# INA.net
KiCad netlist of a schematic drawn in Altium Designer
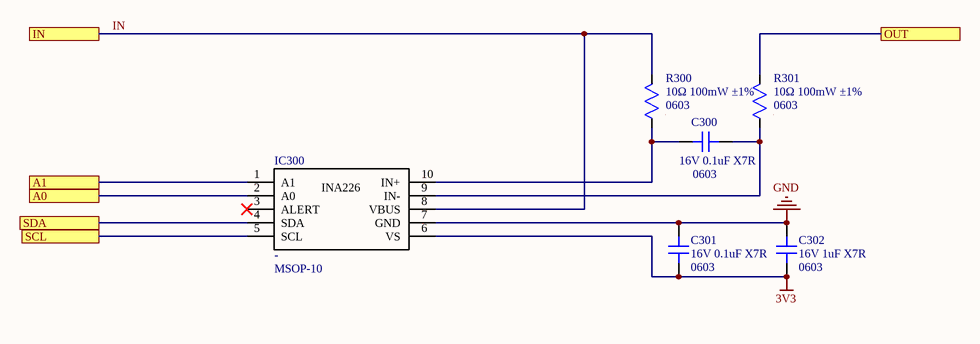
[diagram p0: INA.SchDoc]

(export (version "E")
  (design (tool "Eeschema 10.0.6"))
  (components
    (comp (ref "C300")
      (value "16V 0.1uF X7R")
      (footprint "CAP SMD 0603")
      (description "Condensadores de cerámica multicapa (MLCC- SMD/SMT) WCAP-CSGP 0.1uF 0603 10% 16V MLCC")
      (fields
        (field (name "PACKAGE") "0603")
        (field (name "MPN") "885012206046")
        (field (name "MANUFACTURER") "Wurth Elektronik")
      )
      (libsource (lib "eUSR_Database") (part "CAP non polarized"))
    )
    (comp (ref "C301")
      (value "16V 0.1uF X7R")
      (footprint "CAP SMD 0603")
      (description "Condensadores de cerámica multicapa (MLCC- SMD/SMT) WCAP-CSGP 0.1uF 0603 10% 16V MLCC")
      (fields
        (field (name "PACKAGE") "0603")
        (field (name "MPN") "885012206046")
        (field (name "MANUFACTURER") "Wurth Elektronik")
      )
      (libsource (lib "eUSR_Database") (part "CAP non polarized"))
    )
    (comp (ref "C302")
      (value "16V 1uF X7R")
      (footprint "CAP SMD 0603")
      (description "Condensadores de cerámica multicapa (MLCC- SMD/SMT) WCAP-CSGP 1uF 0603 10% 16V MLCC")
      (fields
        (field (name "PACKAGE") "0603")
        (field (name "MPN") "885012206052")
        (field (name "MANUFACTURER") "Wurth Elektronik")
      )
      (libsource (lib "eUSR_Database") (part "CAP non polarized"))
    )
    (comp (ref "IC300")
      (value "-")
      (footprint "VSOP-10")
      (fields
        (field (name "PACKAGE") "MSOP-10")
        (field (name "MPN") "INA226AIDGSR")
        (field (name "MANUFACTURER") "595-INA226AIDGSR")
        (field (name "Comment") "INA226")
      )
      (libsource (lib "eUSR_Database") (part "INA226"))
    )
    (comp (ref "R300")
      (value "10Ω 100mW ±1%")
      (footprint "RES SMD 0603")
      (description "Resistores de película gruesa - SMD WRIS-RSKS 10 Ohms 1 % 0.1 W 0603 AEC-Q200")
      (fields
        (field (name "PACKAGE") "0603")
        (field (name "MPN") "560112116013")
        (field (name "MANUFACTURER") "Wurth Elektronik")
      )
      (libsource (lib "eUSR_Database") (part "RES"))
    )
    (comp (ref "R301")
      (value "10Ω 100mW ±1%")
      (footprint "RES SMD 0603")
      (description "Resistores de película gruesa - SMD WRIS-RSKS 10 Ohms 1 % 0.1 W 0603 AEC-Q200")
      (fields
        (field (name "PACKAGE") "0603")
        (field (name "MPN") "560112116013")
        (field (name "MANUFACTURER") "Wurth Elektronik")
      )
      (libsource (lib "eUSR_Database") (part "RES"))
    )
  )
  (nets
    (net (code "1") (name "/A0") (class "Default")
      (node (ref "IC300") (pin "2") (pinfunction "A0_2") (pintype "passive"))
    )
    (net (code "2") (name "/A1") (class "Default")
      (node (ref "IC300") (pin "1") (pinfunction "A1_1") (pintype "passive"))
    )
    (net (code "3") (name "/IN") (class "Default")
      (node (ref "IC300") (pin "8") (pinfunction "VBUS_8") (pintype "passive"))
      (node (ref "R300") (pin "2") (pinfunction "2_2") (pintype "passive"))
    )
    (net (code "4") (name "/OUT") (class "Default")
      (node (ref "R301") (pin "2") (pinfunction "2_2") (pintype "passive"))
    )
    (net (code "5") (name "/SCL") (class "Default")
      (node (ref "IC300") (pin "5") (pinfunction "SCL_5") (pintype "passive"))
    )
    (net (code "6") (name "/SDA") (class "Default")
      (node (ref "IC300") (pin "4") (pinfunction "SDA_4") (pintype "passive"))
    )
    (net (code "7") (name "3V3") (class "Default")
      (node (ref "C301") (pin "2") (pinfunction "2_2") (pintype "passive"))
      (node (ref "C302") (pin "2") (pinfunction "2_2") (pintype "passive"))
      (node (ref "IC300") (pin "6") (pinfunction "VS_6") (pintype "passive"))
    )
    (net (code "8") (name "GND") (class "Default")
      (node (ref "C301") (pin "1") (pinfunction "1_1") (pintype "passive"))
      (node (ref "C302") (pin "1") (pinfunction "1_1") (pintype "passive"))
      (node (ref "IC300") (pin "7") (pinfunction "GND_7") (pintype "passive"))
    )
    (net (code "9") (name "Net-(IC300-IN+)") (class "Default")
      (node (ref "C300") (pin "1") (pinfunction "1_1") (pintype "passive"))
      (node (ref "IC300") (pin "10") (pinfunction "IN+_10") (pintype "passive"))
      (node (ref "R300") (pin "1") (pinfunction "1_1") (pintype "passive"))
    )
    (net (code "10") (name "Net-(IC300-IN-)") (class "Default")
      (node (ref "C300") (pin "2") (pinfunction "2_2") (pintype "passive"))
      (node (ref "IC300") (pin "9") (pinfunction "IN-_9") (pintype "passive"))
      (node (ref "R301") (pin "1") (pinfunction "1_1") (pintype "passive"))
    )
    (net (code "11") (name "unconnected-(IC300-ALERT-Pad3)") (class "Default")
      (node (ref "IC300") (pin "3") (pinfunction "ALERT_3") (pintype "passive+no_connect"))
    )
  )
)
